# DRIVERS.net
KiCad netlist of a schematic drawn in Altium Designer
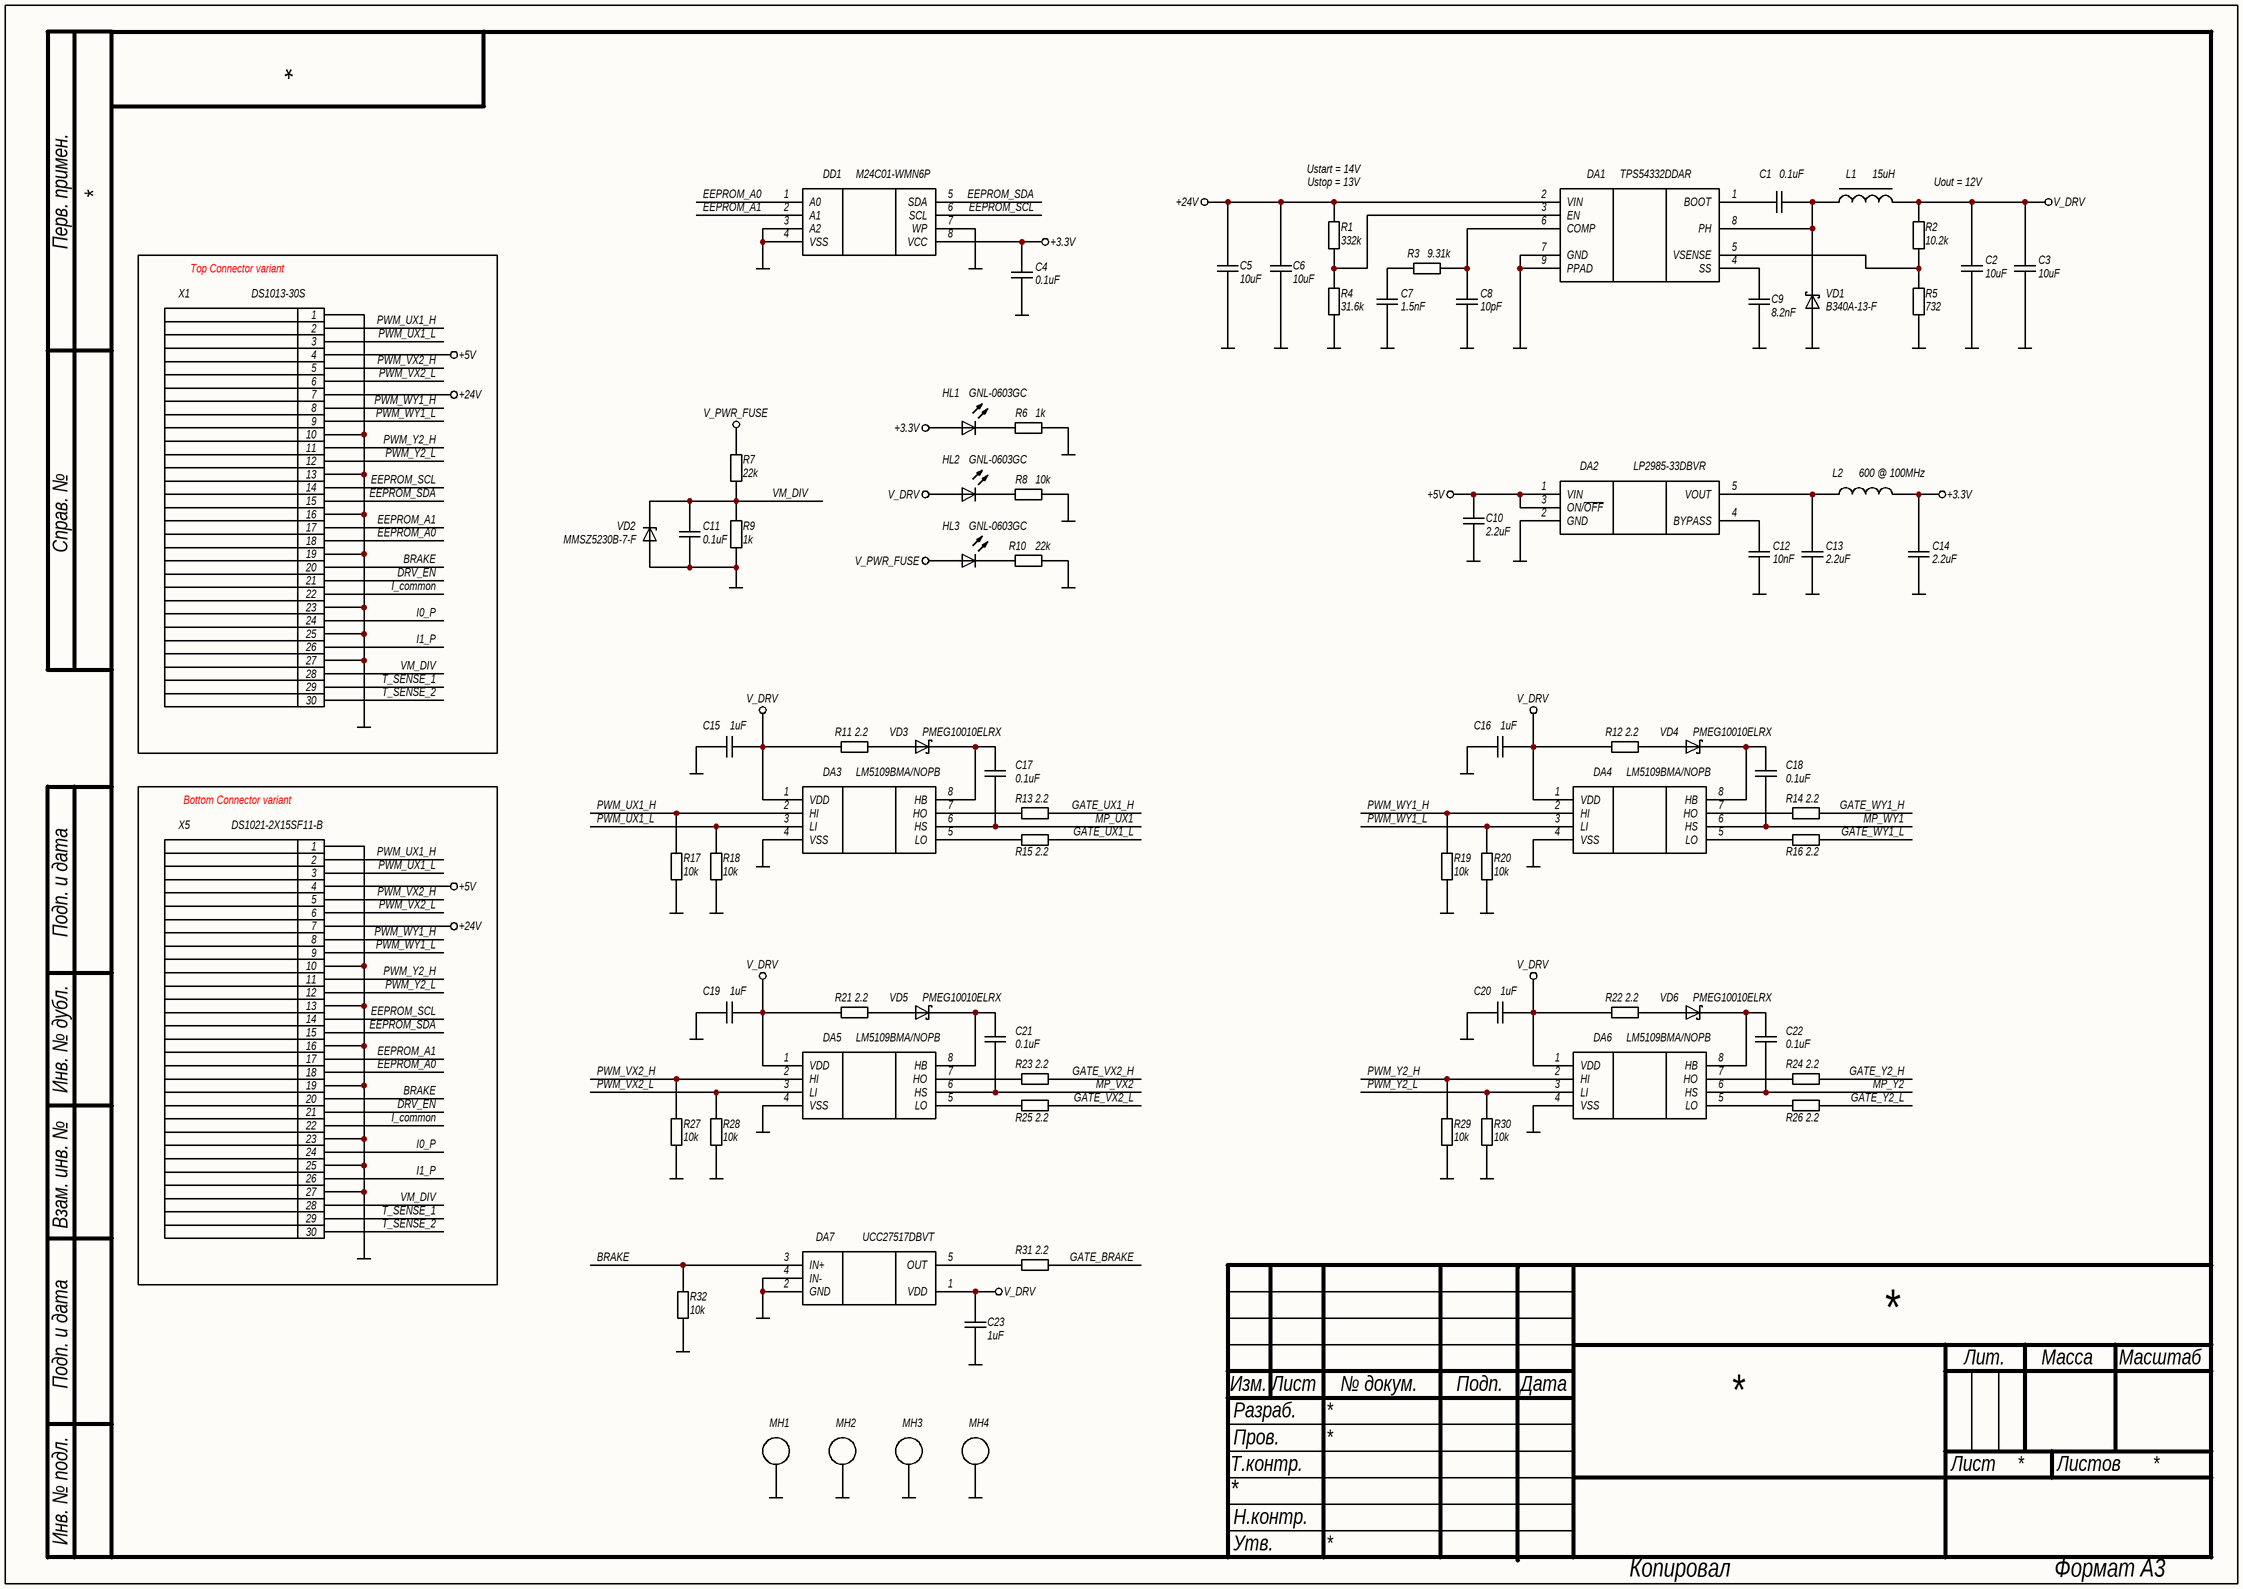
[diagram p0: DRIVERS.SchDoc]

(export (version "E")
  (design (tool "Eeschema 10.0.6"))
  (components
    (comp (ref "C1")
      (value "0.1uF")
      (footprint "C0603N")
      (description "Конденсатор")
      (libsource (lib "Components Library") (part "CAP_FIXED"))
    )
    (comp (ref "C2")
      (value "10uF")
      (footprint "C0805N")
      (description "Конденсатор")
      (libsource (lib "Components Library") (part "CAP_FIXED"))
    )
    (comp (ref "C3")
      (value "10uF")
      (footprint "C0805N")
      (description "Конденсатор")
      (libsource (lib "Components Library") (part "CAP_FIXED"))
    )
    (comp (ref "C4")
      (value "0.1uF")
      (footprint "C0603N")
      (description "Конденсатор")
      (libsource (lib "Components Library") (part "CAP_FIXED"))
    )
    (comp (ref "C5")
      (value "10uF")
      (footprint "C1206N")
      (description "Конденсатор")
      (libsource (lib "Components Library") (part "CAP_FIXED"))
    )
    (comp (ref "C6")
      (value "10uF")
      (footprint "C1206N")
      (description "Конденсатор")
      (libsource (lib "Components Library") (part "CAP_FIXED"))
    )
    (comp (ref "C7")
      (value "1.5nF")
      (footprint "C0603N")
      (description "Конденсатор")
      (libsource (lib "Components Library") (part "CAP_FIXED"))
    )
    (comp (ref "C8")
      (value "10pF")
      (footprint "C0603N")
      (description "Конденсатор")
      (libsource (lib "Components Library") (part "CAP_FIXED"))
    )
    (comp (ref "C9")
      (value "8.2nF")
      (footprint "C0603N")
      (description "Конденсатор")
      (libsource (lib "Components Library") (part "CAP_FIXED"))
    )
    (comp (ref "C10")
      (value "2.2uF")
      (footprint "C0603N")
      (description "Конденсатор")
      (libsource (lib "Components Library") (part "CAP_FIXED"))
    )
    (comp (ref "C11")
      (value "0.1uF")
      (footprint "C0603N")
      (description "Конденсатор")
      (libsource (lib "Components Library") (part "CAP_FIXED"))
    )
    (comp (ref "C12")
      (value "10nF")
      (footprint "C0603N")
      (description "Конденсатор")
      (libsource (lib "Components Library") (part "CAP_FIXED"))
    )
    (comp (ref "C13")
      (value "2.2uF")
      (footprint "C0603N")
      (description "Конденсатор")
      (libsource (lib "Components Library") (part "CAP_FIXED"))
    )
    (comp (ref "C14")
      (value "2.2uF")
      (footprint "C0603N")
      (description "Конденсатор")
      (libsource (lib "Components Library") (part "CAP_FIXED"))
    )
    (comp (ref "C15")
      (value "1uF")
      (footprint "C0805N")
      (description "Конденсатор")
      (libsource (lib "Components Library") (part "CAP_FIXED"))
    )
    (comp (ref "C16")
      (value "1uF")
      (footprint "C0805N")
      (description "Конденсатор")
      (libsource (lib "Components Library") (part "CAP_FIXED"))
    )
    (comp (ref "C17")
      (value "0.1uF")
      (footprint "C0603N")
      (description "Конденсатор")
      (libsource (lib "Components Library") (part "CAP_FIXED"))
    )
    (comp (ref "C18")
      (value "0.1uF")
      (footprint "C0603N")
      (description "Конденсатор")
      (libsource (lib "Components Library") (part "CAP_FIXED"))
    )
    (comp (ref "C19")
      (value "1uF")
      (footprint "C0805N")
      (description "Конденсатор")
      (libsource (lib "Components Library") (part "CAP_FIXED"))
    )
    (comp (ref "C20")
      (value "1uF")
      (footprint "C0805N")
      (description "Конденсатор")
      (libsource (lib "Components Library") (part "CAP_FIXED"))
    )
    (comp (ref "C21")
      (value "0.1uF")
      (footprint "C0603N")
      (description "Конденсатор")
      (libsource (lib "Components Library") (part "CAP_FIXED"))
    )
    (comp (ref "C22")
      (value "0.1uF")
      (footprint "C0603N")
      (description "Конденсатор")
      (libsource (lib "Components Library") (part "CAP_FIXED"))
    )
    (comp (ref "C23")
      (value "1uF")
      (footprint "C0805N")
      (description "Конденсатор")
      (libsource (lib "Components Library") (part "CAP_FIXED"))
    )
    (comp (ref "DA1")
      (value "TPS54332DDAR")
      (footprint "SOIC8-EP")
      (description "Микросхема понижающего преобразователя")
      (libsource (lib "Components Library") (part "TPS54332"))
    )
    (comp (ref "DA2")
      (value "LP2985-33DBVR")
      (footprint "DBV0005A (SOT23-5)")
      (description "Микросхема стабилизатор напряжения положительной полярности")
      (libsource (lib "Components Library") (part "LP2985"))
    )
    (comp (ref "DA3")
      (value "LM5109BMA/NOPB")
      (footprint "D0008A")
      (description "Микросхема драйвер затворов нижнего и верхнего ключа")
      (libsource (lib "Components Library") (part "LM5109"))
    )
    (comp (ref "DA4")
      (value "LM5109BMA/NOPB")
      (footprint "D0008A")
      (description "Микросхема драйвер затворов нижнего и верхнего ключа")
      (libsource (lib "Components Library") (part "LM5109"))
    )
    (comp (ref "DA5")
      (value "LM5109BMA/NOPB")
      (footprint "D0008A")
      (description "Микросхема драйвер затворов нижнего и верхнего ключа")
      (libsource (lib "Components Library") (part "LM5109"))
    )
    (comp (ref "DA6")
      (value "LM5109BMA/NOPB")
      (footprint "D0008A")
      (description "Микросхема драйвер затворов нижнего и верхнего ключа")
      (libsource (lib "Components Library") (part "LM5109"))
    )
    (comp (ref "DA7")
      (value "UCC27517DBVT")
      (footprint "DBV0005A (SOT23-5)")
      (description "Микросхема драйвер затвора нижнего ключа")
      (libsource (lib "Components Library") (part "UCC27517"))
    )
    (comp (ref "DD1")
      (value "M24C01-WMN6P")
      (footprint "SOIC8")
      (description "Микросхема EEPROM с I2C интерфейсом")
      (libsource (lib "Components Library") (part "EEPROM_I2C"))
    )
    (comp (ref "HL1")
      (value "GNL-0603GC")
      (footprint "LED0603")
      (description "Светодиод")
      (libsource (lib "Components Library") (part "LED"))
    )
    (comp (ref "HL2")
      (value "GNL-0603GC")
      (footprint "LED0603")
      (description "Светодиод")
      (libsource (lib "Components Library") (part "LED"))
    )
    (comp (ref "HL3")
      (value "GNL-0603GC")
      (footprint "LED0603")
      (description "Светодиод")
      (libsource (lib "Components Library") (part "LED"))
    )
    (comp (ref "L1")
      (value "15uH")
      (footprint "SRN8040")
      (description "Дроссель с магнитопроводом")
      (libsource (lib "Components Library") (part "IND_CORE"))
    )
    (comp (ref "L2")
      (value "600 @ 100MHz")
      (footprint "FB0603N")
      (description "Фильтр ЭМП индуктивный")
      (libsource (lib "Components Library") (part "IND_FILTER"))
    )
    (comp (ref "MH1")
      (value "MNT_HOLE_PL")
      (footprint "MH_3.2_5.4_PLATED_VIA")
      (description "Монтажное отверстие, металлизированное")
      (libsource (lib "Components Library") (part "MNT_HOLE_PL"))
    )
    (comp (ref "MH2")
      (value "MNT_HOLE_PL")
      (footprint "MH_3.2_5.4_PLATED_VIA")
      (description "Монтажное отверстие, металлизированное")
      (libsource (lib "Components Library") (part "MNT_HOLE_PL"))
    )
    (comp (ref "MH3")
      (value "MNT_HOLE_PL")
      (footprint "MH_3.2_5.4_PLATED_VIA")
      (description "Монтажное отверстие, металлизированное")
      (libsource (lib "Components Library") (part "MNT_HOLE_PL"))
    )
    (comp (ref "MH4")
      (value "MNT_HOLE_PL")
      (footprint "MH_3.2_5.4_PLATED_VIA")
      (description "Монтажное отверстие, металлизированное")
      (libsource (lib "Components Library") (part "MNT_HOLE_PL"))
    )
    (comp (ref "R1")
      (value "332k")
      (footprint "R0603N")
      (description "Резистор")
      (libsource (lib "Components Library") (part "RES_FIXED"))
    )
    (comp (ref "R2")
      (value "10.2k")
      (footprint "R0603N")
      (description "Резистор")
      (libsource (lib "Components Library") (part "RES_FIXED"))
    )
    (comp (ref "R3")
      (value "9.31k")
      (footprint "R0603N")
      (description "Резистор")
      (libsource (lib "") (part "RES_FIXED_1"))
    )
    (comp (ref "R4")
      (value "31.6k")
      (footprint "R0603N")
      (description "Резистор")
      (libsource (lib "Components Library") (part "RES_FIXED"))
    )
    (comp (ref "R5")
      (value "732")
      (footprint "R0603N")
      (description "Резистор")
      (libsource (lib "Components Library") (part "RES_FIXED"))
    )
    (comp (ref "R6")
      (value "1k")
      (footprint "R0603N")
      (description "Резистор")
      (libsource (lib "") (part "RES_FIXED_2"))
    )
    (comp (ref "R7")
      (value "22k")
      (footprint "R0603N")
      (description "Резистор")
      (libsource (lib "Components Library") (part "RES_FIXED"))
    )
    (comp (ref "R8")
      (value "10k")
      (footprint "R0603N")
      (description "Резистор")
      (libsource (lib "") (part "RES_FIXED_2"))
    )
    (comp (ref "R9")
      (value "1k")
      (footprint "R0603N")
      (description "Резистор")
      (libsource (lib "Components Library") (part "RES_FIXED"))
    )
    (comp (ref "R10")
      (value "22k")
      (footprint "R0603N")
      (description "Резистор")
      (libsource (lib "") (part "RES_FIXED_2"))
    )
    (comp (ref "R11")
      (value "2.2")
      (footprint "R0603N")
      (description "Резистор")
      (libsource (lib "") (part "RES_FIXED_1"))
    )
    (comp (ref "R12")
      (value "2.2")
      (footprint "R0603N")
      (description "Резистор")
      (libsource (lib "") (part "RES_FIXED_1"))
    )
    (comp (ref "R13")
      (value "2.2")
      (footprint "R0603N")
      (description "Резистор")
      (libsource (lib "") (part "RES_FIXED_1"))
    )
    (comp (ref "R14")
      (value "2.2")
      (footprint "R0603N")
      (description "Резистор")
      (libsource (lib "") (part "RES_FIXED_1"))
    )
    (comp (ref "R15")
      (value "2.2")
      (footprint "R0603N")
      (description "Резистор")
      (libsource (lib "") (part "RES_FIXED_1"))
    )
    (comp (ref "R16")
      (value "2.2")
      (footprint "R0603N")
      (description "Резистор")
      (libsource (lib "") (part "RES_FIXED_1"))
    )
    (comp (ref "R17")
      (value "10k")
      (footprint "R0603N")
      (description "Резистор")
      (libsource (lib "Components Library") (part "RES_FIXED"))
    )
    (comp (ref "R18")
      (value "10k")
      (footprint "R0603N")
      (description "Резистор")
      (libsource (lib "Components Library") (part "RES_FIXED"))
    )
    (comp (ref "R19")
      (value "10k")
      (footprint "R0603N")
      (description "Резистор")
      (libsource (lib "Components Library") (part "RES_FIXED"))
    )
    (comp (ref "R20")
      (value "10k")
      (footprint "R0603N")
      (description "Резистор")
      (libsource (lib "Components Library") (part "RES_FIXED"))
    )
    (comp (ref "R21")
      (value "2.2")
      (footprint "R0603N")
      (description "Резистор")
      (libsource (lib "") (part "RES_FIXED_1"))
    )
    (comp (ref "R22")
      (value "2.2")
      (footprint "R0603N")
      (description "Резистор")
      (libsource (lib "") (part "RES_FIXED_1"))
    )
    (comp (ref "R23")
      (value "2.2")
      (footprint "R0603N")
      (description "Резистор")
      (libsource (lib "") (part "RES_FIXED_1"))
    )
    (comp (ref "R24")
      (value "2.2")
      (footprint "R0603N")
      (description "Резистор")
      (libsource (lib "") (part "RES_FIXED_1"))
    )
    (comp (ref "R25")
      (value "2.2")
      (footprint "R0603N")
      (description "Резистор")
      (libsource (lib "") (part "RES_FIXED_1"))
    )
    (comp (ref "R26")
      (value "2.2")
      (footprint "R0603N")
      (description "Резистор")
      (libsource (lib "") (part "RES_FIXED_1"))
    )
    (comp (ref "R27")
      (value "10k")
      (footprint "R0603N")
      (description "Резистор")
      (libsource (lib "Components Library") (part "RES_FIXED"))
    )
    (comp (ref "R28")
      (value "10k")
      (footprint "R0603N")
      (description "Резистор")
      (libsource (lib "Components Library") (part "RES_FIXED"))
    )
    (comp (ref "R29")
      (value "10k")
      (footprint "R0603N")
      (description "Резистор")
      (libsource (lib "Components Library") (part "RES_FIXED"))
    )
    (comp (ref "R30")
      (value "10k")
      (footprint "R0603N")
      (description "Резистор")
      (libsource (lib "Components Library") (part "RES_FIXED"))
    )
    (comp (ref "R31")
      (value "2.2")
      (footprint "R0603N")
      (description "Резистор")
      (libsource (lib "") (part "RES_FIXED_1"))
    )
    (comp (ref "R32")
      (value "10k")
      (footprint "R0603N")
      (description "Резистор")
      (libsource (lib "Components Library") (part "RES_FIXED"))
    )
    (comp (ref "VD1")
      (value "B340A-13-F")
      (footprint "SMA")
      (description "Диод Шоттки")
      (libsource (lib "Components Library") (part "SCHOTTKY"))
    )
    (comp (ref "VD2")
      (value "MMSZ5230B-7-F")
      (footprint "SOD123")
      (description "Стабилитрон")
      (libsource (lib "Components Library") (part "ZENER"))
    )
    (comp (ref "VD3")
      (value "PMEG10010ELRX")
      (footprint "SOD123W")
      (description "Диод Шоттки")
      (libsource (lib "Components Library") (part "SCHOTTKY"))
    )
    (comp (ref "VD4")
      (value "PMEG10010ELRX")
      (footprint "SOD123W")
      (description "Диод Шоттки")
      (libsource (lib "Components Library") (part "SCHOTTKY"))
    )
    (comp (ref "VD5")
      (value "PMEG10010ELRX")
      (footprint "SOD123W")
      (description "Диод Шоттки")
      (libsource (lib "Components Library") (part "SCHOTTKY"))
    )
    (comp (ref "VD6")
      (value "PMEG10010ELRX")
      (footprint "SOD123W")
      (description "Диод Шоттки")
      (libsource (lib "Components Library") (part "SCHOTTKY"))
    )
    (comp (ref "X1")
      (value "DS1013-30S")
      (footprint "2.54_2X15_HEADER_BOX")
      (description "Разъем, 30 контактов")
      (libsource (lib "Components Library") (part "Connector 30"))
    )
    (comp (ref "X5")
      (value "DS1021-2X15SF11-B")
      (footprint "2.54_2X15_HEADER")
      (description "Разъем, 30 контактов")
      (libsource (lib "Components Library") (part "Connector 30"))
    )
  )
  (nets
    (net (code "1") (name "+3.3V") (class "Default")
      (node (ref "C14") (pin "2") (pinfunction "2_2") (pintype "passive"))
      (node (ref "C4") (pin "2") (pinfunction "2_2") (pintype "passive"))
      (node (ref "DD1") (pin "8") (pinfunction "VCC_8") (pintype "power_in"))
      (node (ref "HL1") (pin "2") (pinfunction "A_2") (pintype "passive"))
      (node (ref "L2") (pin "2") (pinfunction "2_2") (pintype "passive"))
    )
    (net (code "2") (name "+5V") (class "Default")
      (node (ref "C10") (pin "2") (pinfunction "2_2") (pintype "passive"))
      (node (ref "DA2") (pin "1") (pinfunction "VIN_1") (pintype "power_in"))
      (node (ref "DA2") (pin "3") (pinfunction "ON/~{OFF}_3") (pintype "power_in"))
      (node (ref "X1") (pin "4") (pinfunction "4_4") (pintype "power_in"))
      (node (ref "X5") (pin "4") (pinfunction "4_4") (pintype "power_in"))
    )
    (net (code "3") (name "+24V") (class "Default")
      (node (ref "C5") (pin "2") (pinfunction "2_2") (pintype "passive"))
      (node (ref "C6") (pin "2") (pinfunction "2_2") (pintype "passive"))
      (node (ref "DA1") (pin "2") (pinfunction "VIN_2") (pintype "power_in"))
      (node (ref "R1") (pin "1") (pinfunction "1_1") (pintype "passive"))
      (node (ref "X1") (pin "7") (pinfunction "7_7") (pintype "power_in"))
      (node (ref "X5") (pin "7") (pinfunction "7_7") (pintype "power_in"))
    )
    (net (code "4") (name "/BRAKE") (class "Default")
      (node (ref "DA7") (pin "3") (pinfunction "IN+_3") (pintype "power_in"))
      (node (ref "R32") (pin "1") (pinfunction "1_1") (pintype "passive"))
      (node (ref "X1") (pin "20") (pinfunction "20_20") (pintype "power_in"))
      (node (ref "X5") (pin "20") (pinfunction "20_20") (pintype "power_in"))
    )
    (net (code "5") (name "/DRV_EN") (class "Default")
      (node (ref "X1") (pin "21") (pinfunction "21_21") (pintype "power_in"))
      (node (ref "X5") (pin "21") (pinfunction "21_21") (pintype "power_in"))
    )
    (net (code "6") (name "/EEPROM_A0") (class "Default")
      (node (ref "DD1") (pin "1") (pinfunction "A0_1") (pintype "power_in"))
      (node (ref "X1") (pin "18") (pinfunction "18_18") (pintype "power_in"))
      (node (ref "X5") (pin "18") (pinfunction "18_18") (pintype "power_in"))
    )
    (net (code "7") (name "/EEPROM_A1") (class "Default")
      (node (ref "DD1") (pin "2") (pinfunction "A1_2") (pintype "power_in"))
      (node (ref "X1") (pin "17") (pinfunction "17_17") (pintype "power_in"))
      (node (ref "X5") (pin "17") (pinfunction "17_17") (pintype "power_in"))
    )
    (net (code "8") (name "/EEPROM_SCL") (class "Default")
      (node (ref "DD1") (pin "6") (pinfunction "SCL_6") (pintype "power_in"))
      (node (ref "X1") (pin "14") (pinfunction "14_14") (pintype "power_in"))
      (node (ref "X5") (pin "14") (pinfunction "14_14") (pintype "power_in"))
    )
    (net (code "9") (name "/EEPROM_SDA") (class "Default")
      (node (ref "DD1") (pin "5") (pinfunction "SDA_5") (pintype "power_in"))
      (node (ref "X1") (pin "15") (pinfunction "15_15") (pintype "power_in"))
      (node (ref "X5") (pin "15") (pinfunction "15_15") (pintype "power_in"))
    )
    (net (code "10") (name "/GATE_BRAKE") (class "Default")
      (node (ref "R31") (pin "1") (pinfunction "1_1") (pintype "passive"))
    )
    (net (code "11") (name "/GATE_UX1_H") (class "Default")
      (node (ref "R13") (pin "1") (pinfunction "1_1") (pintype "passive"))
    )
    (net (code "12") (name "/GATE_UX1_L") (class "Default")
      (node (ref "R15") (pin "1") (pinfunction "1_1") (pintype "passive"))
    )
    (net (code "13") (name "/GATE_VX2_H") (class "Default")
      (node (ref "R23") (pin "1") (pinfunction "1_1") (pintype "passive"))
    )
    (net (code "14") (name "/GATE_VX2_L") (class "Default")
      (node (ref "R25") (pin "1") (pinfunction "1_1") (pintype "passive"))
    )
    (net (code "15") (name "/GATE_WY1_H") (class "Default")
      (node (ref "R14") (pin "1") (pinfunction "1_1") (pintype "passive"))
    )
    (net (code "16") (name "/GATE_WY1_L") (class "Default")
      (node (ref "R16") (pin "1") (pinfunction "1_1") (pintype "passive"))
    )
    (net (code "17") (name "/GATE_Y2_H") (class "Default")
      (node (ref "R24") (pin "1") (pinfunction "1_1") (pintype "passive"))
    )
    (net (code "18") (name "/GATE_Y2_L") (class "Default")
      (node (ref "R26") (pin "1") (pinfunction "1_1") (pintype "passive"))
    )
    (net (code "19") (name "/I0_P") (class "Default")
      (node (ref "X1") (pin "24") (pinfunction "24_24") (pintype "power_in"))
      (node (ref "X5") (pin "24") (pinfunction "24_24") (pintype "power_in"))
    )
    (net (code "20") (name "/I1_P") (class "Default")
      (node (ref "X1") (pin "26") (pinfunction "26_26") (pintype "power_in"))
      (node (ref "X5") (pin "26") (pinfunction "26_26") (pintype "power_in"))
    )
    (net (code "21") (name "/I_common") (class "Default")
      (node (ref "X1") (pin "22") (pinfunction "22_22") (pintype "power_in"))
      (node (ref "X5") (pin "22") (pinfunction "22_22") (pintype "power_in"))
    )
    (net (code "22") (name "/MP_UX1") (class "Default")
      (node (ref "C17") (pin "2") (pinfunction "2_2") (pintype "passive"))
      (node (ref "DA3") (pin "6") (pinfunction "HS_6") (pintype "power_in"))
    )
    (net (code "23") (name "/MP_VX2") (class "Default")
      (node (ref "C21") (pin "2") (pinfunction "2_2") (pintype "passive"))
      (node (ref "DA5") (pin "6") (pinfunction "HS_6") (pintype "power_in"))
    )
    (net (code "24") (name "/MP_WY1") (class "Default")
      (node (ref "C18") (pin "2") (pinfunction "2_2") (pintype "passive"))
      (node (ref "DA4") (pin "6") (pinfunction "HS_6") (pintype "power_in"))
    )
    (net (code "25") (name "/MP_Y2") (class "Default")
      (node (ref "C22") (pin "2") (pinfunction "2_2") (pintype "passive"))
      (node (ref "DA6") (pin "6") (pinfunction "HS_6") (pintype "power_in"))
    )
    (net (code "26") (name "/PWM_UX1_H") (class "Default")
      (node (ref "DA3") (pin "2") (pinfunction "HI_2") (pintype "power_in"))
      (node (ref "R17") (pin "1") (pinfunction "1_1") (pintype "passive"))
      (node (ref "X1") (pin "2") (pinfunction "2_2") (pintype "power_in"))
      (node (ref "X5") (pin "2") (pinfunction "2_2") (pintype "power_in"))
    )
    (net (code "27") (name "/PWM_UX1_L") (class "Default")
      (node (ref "DA3") (pin "3") (pinfunction "LI_3") (pintype "power_in"))
      (node (ref "R18") (pin "1") (pinfunction "1_1") (pintype "passive"))
      (node (ref "X1") (pin "3") (pinfunction "3_3") (pintype "power_in"))
      (node (ref "X5") (pin "3") (pinfunction "3_3") (pintype "power_in"))
    )
    (net (code "28") (name "/PWM_VX2_H") (class "Default")
      (node (ref "DA5") (pin "2") (pinfunction "HI_2") (pintype "power_in"))
      (node (ref "R27") (pin "1") (pinfunction "1_1") (pintype "passive"))
      (node (ref "X1") (pin "5") (pinfunction "5_5") (pintype "power_in"))
      (node (ref "X5") (pin "5") (pinfunction "5_5") (pintype "power_in"))
    )
    (net (code "29") (name "/PWM_VX2_L") (class "Default")
      (node (ref "DA5") (pin "3") (pinfunction "LI_3") (pintype "power_in"))
      (node (ref "R28") (pin "1") (pinfunction "1_1") (pintype "passive"))
      (node (ref "X1") (pin "6") (pinfunction "6_6") (pintype "power_in"))
      (node (ref "X5") (pin "6") (pinfunction "6_6") (pintype "power_in"))
    )
    (net (code "30") (name "/PWM_WY1_H") (class "Default")
      (node (ref "DA4") (pin "2") (pinfunction "HI_2") (pintype "power_in"))
      (node (ref "R19") (pin "1") (pinfunction "1_1") (pintype "passive"))
      (node (ref "X1") (pin "8") (pinfunction "8_8") (pintype "power_in"))
      (node (ref "X5") (pin "8") (pinfunction "8_8") (pintype "power_in"))
    )
    (net (code "31") (name "/PWM_WY1_L") (class "Default")
      (node (ref "DA4") (pin "3") (pinfunction "LI_3") (pintype "power_in"))
      (node (ref "R20") (pin "1") (pinfunction "1_1") (pintype "passive"))
      (node (ref "X1") (pin "9") (pinfunction "9_9") (pintype "power_in"))
      (node (ref "X5") (pin "9") (pinfunction "9_9") (pintype "power_in"))
    )
    (net (code "32") (name "/PWM_Y2_H") (class "Default")
      (node (ref "DA6") (pin "2") (pinfunction "HI_2") (pintype "power_in"))
      (node (ref "R29") (pin "1") (pinfunction "1_1") (pintype "passive"))
      (node (ref "X1") (pin "11") (pinfunction "11_11") (pintype "power_in"))
      (node (ref "X5") (pin "11") (pinfunction "11_11") (pintype "power_in"))
    )
    (net (code "33") (name "/PWM_Y2_L") (class "Default")
      (node (ref "DA6") (pin "3") (pinfunction "LI_3") (pintype "power_in"))
      (node (ref "R30") (pin "1") (pinfunction "1_1") (pintype "passive"))
      (node (ref "X1") (pin "12") (pinfunction "12_12") (pintype "power_in"))
      (node (ref "X5") (pin "12") (pinfunction "12_12") (pintype "power_in"))
    )
    (net (code "34") (name "/T_SENSE_1") (class "Default")
      (node (ref "X1") (pin "29") (pinfunction "29_29") (pintype "power_in"))
      (node (ref "X5") (pin "29") (pinfunction "29_29") (pintype "power_in"))
    )
    (net (code "35") (name "/T_SENSE_2") (class "Default")
      (node (ref "X1") (pin "30") (pinfunction "30_30") (pintype "power_in"))
      (node (ref "X5") (pin "30") (pinfunction "30_30") (pintype "power_in"))
    )
    (net (code "36") (name "/VM_DIV") (class "Default")
      (node (ref "C11") (pin "2") (pinfunction "2_2") (pintype "passive"))
      (node (ref "R7") (pin "2") (pinfunction "2_2") (pintype "passive"))
      (node (ref "R9") (pin "1") (pinfunction "1_1") (pintype "passive"))
      (node (ref "VD2") (pin "1") (pinfunction "K_1") (pintype "passive"))
      (node (ref "X1") (pin "28") (pinfunction "28_28") (pintype "power_in"))
      (node (ref "X5") (pin "28") (pinfunction "28_28") (pintype "power_in"))
    )
    (net (code "37") (name "GND") (class "Default")
      (node (ref "C10") (pin "1") (pinfunction "1_1") (pintype "passive"))
      (node (ref "C11") (pin "1") (pinfunction "1_1") (pintype "passive"))
      (node (ref "C12") (pin "1") (pinfunction "1_1") (pintype "passive"))
      (node (ref "C13") (pin "1") (pinfunction "1_1") (pintype "passive"))
      (node (ref "C14") (pin "1") (pinfunction "1_1") (pintype "passive"))
      (node (ref "C15") (pin "2") (pinfunction "2_2") (pintype "passive"))
      (node (ref "C16") (pin "2") (pinfunction "2_2") (pintype "passive"))
      (node (ref "C19") (pin "2") (pinfunction "2_2") (pintype "passive"))
      (node (ref "C2") (pin "2") (pinfunction "2_2") (pintype "passive"))
      (node (ref "C20") (pin "2") (pinfunction "2_2") (pintype "passive"))
      (node (ref "C23") (pin "2") (pinfunction "2_2") (pintype "passive"))
      (node (ref "C3") (pin "1") (pinfunction "1_1") (pintype "passive"))
      (node (ref "C4") (pin "1") (pinfunction "1_1") (pintype "passive"))
      (node (ref "C5") (pin "1") (pinfunction "1_1") (pintype "passive"))
      (node (ref "C6") (pin "1") (pinfunction "1_1") (pintype "passive"))
      (node (ref "C7") (pin "1") (pinfunction "1_1") (pintype "passive"))
      (node (ref "C8") (pin "1") (pinfunction "1_1") (pintype "passive"))
      (node (ref "C9") (pin "1") (pinfunction "1_1") (pintype "passive"))
      (node (ref "DA1") (pin "7") (pinfunction "GND_7") (pintype "power_in"))
      (node (ref "DA1") (pin "9") (pinfunction "PPAD_9") (pintype "power_in"))
      (node (ref "DA2") (pin "2") (pinfunction "GND_2") (pintype "power_in"))
      (node (ref "DA3") (pin "4") (pinfunction "VSS_4") (pintype "power_in"))
      (node (ref "DA4") (pin "4") (pinfunction "VSS_4") (pintype "power_in"))
      (node (ref "DA5") (pin "4") (pinfunction "VSS_4") (pintype "power_in"))
      (node (ref "DA6") (pin "4") (pinfunction "VSS_4") (pintype "power_in"))
      (node (ref "DA7") (pin "2") (pinfunction "GND_2") (pintype "power_in"))
      (node (ref "DA7") (pin "4") (pinfunction "IN-_4") (pintype "power_in"))
      (node (ref "DD1") (pin "3") (pinfunction "A2_3") (pintype "power_in"))
      (node (ref "DD1") (pin "4") (pinfunction "VSS_4") (pintype "power_in"))
      (node (ref "DD1") (pin "7") (pinfunction "WP_7") (pintype "power_in"))
      (node (ref "MH1") (pin "1") (pinfunction "1_1") (pintype "passive"))
      (node (ref "MH2") (pin "1") (pinfunction "1_1") (pintype "passive"))
      (node (ref "MH3") (pin "1") (pinfunction "1_1") (pintype "passive"))
      (node (ref "MH4") (pin "1") (pinfunction "1_1") (pintype "passive"))
      (node (ref "R10") (pin "2") (pinfunction "2_2") (pintype "passive"))
      (node (ref "R17") (pin "2") (pinfunction "2_2") (pintype "passive"))
      (node (ref "R18") (pin "2") (pinfunction "2_2") (pintype "passive"))
      (node (ref "R19") (pin "2") (pinfunction "2_2") (pintype "passive"))
      (node (ref "R20") (pin "2") (pinfunction "2_2") (pintype "passive"))
      (node (ref "R27") (pin "2") (pinfunction "2_2") (pintype "passive"))
      (node (ref "R28") (pin "2") (pinfunction "2_2") (pintype "passive"))
      (node (ref "R29") (pin "2") (pinfunction "2_2") (pintype "passive"))
      (node (ref "R30") (pin "2") (pinfunction "2_2") (pintype "passive"))
      (node (ref "R32") (pin "2") (pinfunction "2_2") (pintype "passive"))
      (node (ref "R4") (pin "2") (pinfunction "2_2") (pintype "passive"))
      (node (ref "R5") (pin "2") (pinfunction "2_2") (pintype "passive"))
      (node (ref "R6") (pin "2") (pinfunction "2_2") (pintype "passive"))
      (node (ref "R8") (pin "2") (pinfunction "2_2") (pintype "passive"))
      (node (ref "R9") (pin "2") (pinfunction "2_2") (pintype "passive"))
      (node (ref "VD1") (pin "2") (pinfunction "A_2") (pintype "passive"))
      (node (ref "VD2") (pin "2") (pinfunction "A_2") (pintype "passive"))
      (node (ref "X1") (pin "1") (pinfunction "1_1") (pintype "power_in"))
      (node (ref "X1") (pin "10") (pinfunction "10_10") (pintype "power_in"))
      (node (ref "X1") (pin "13") (pinfunction "13_13") (pintype "power_in"))
      (node (ref "X1") (pin "16") (pinfunction "16_16") (pintype "power_in"))
      (node (ref "X1") (pin "19") (pinfunction "19_19") (pintype "power_in"))
      (node (ref "X1") (pin "23") (pinfunction "23_23") (pintype "power_in"))
      (node (ref "X1") (pin "25") (pinfunction "25_25") (pintype "power_in"))
      (node (ref "X1") (pin "27") (pinfunction "27_27") (pintype "power_in"))
      (node (ref "X5") (pin "1") (pinfunction "1_1") (pintype "power_in"))
      (node (ref "X5") (pin "10") (pinfunction "10_10") (pintype "power_in"))
      (node (ref "X5") (pin "13") (pinfunction "13_13") (pintype "power_in"))
      (node (ref "X5") (pin "16") (pinfunction "16_16") (pintype "power_in"))
      (node (ref "X5") (pin "19") (pinfunction "19_19") (pintype "power_in"))
      (node (ref "X5") (pin "23") (pinfunction "23_23") (pintype "power_in"))
      (node (ref "X5") (pin "25") (pinfunction "25_25") (pintype "power_in"))
      (node (ref "X5") (pin "27") (pinfunction "27_27") (pintype "power_in"))
    )
    (net (code "38") (name "Net-(C7-Pad2)") (class "Default")
      (node (ref "C7") (pin "2") (pinfunction "2_2") (pintype "passive"))
      (node (ref "R3") (pin "2") (pinfunction "2_2") (pintype "passive"))
    )
    (net (code "39") (name "Net-(DA1-BOOT)") (class "Default")
      (node (ref "C1") (pin "1") (pinfunction "1_1") (pintype "passive"))
      (node (ref "DA1") (pin "1") (pinfunction "BOOT_1") (pintype "power_in"))
    )
    (net (code "40") (name "Net-(DA1-COMP)") (class "Default")
      (node (ref "C8") (pin "2") (pinfunction "2_2") (pintype "passive"))
      (node (ref "DA1") (pin "6") (pinfunction "COMP_6") (pintype "power_in"))
      (node (ref "R3") (pin "1") (pinfunction "1_1") (pintype "passive"))
    )
    (net (code "41") (name "Net-(DA1-EN)") (class "Default")
      (node (ref "DA1") (pin "3") (pinfunction "EN_3") (pintype "power_in"))
      (node (ref "R1") (pin "2") (pinfunction "2_2") (pintype "passive"))
      (node (ref "R4") (pin "1") (pinfunction "1_1") (pintype "passive"))
    )
    (net (code "42") (name "Net-(DA1-PH)") (class "Default")
      (node (ref "C1") (pin "2") (pinfunction "2_2") (pintype "passive"))
      (node (ref "DA1") (pin "8") (pinfunction "PH_8") (pintype "power_in"))
      (node (ref "L1") (pin "1") (pinfunction "1_1") (pintype "passive"))
      (node (ref "VD1") (pin "1") (pinfunction "K_1") (pintype "passive"))
    )
    (net (code "43") (name "Net-(DA1-SS)") (class "Default")
      (node (ref "C9") (pin "2") (pinfunction "2_2") (pintype "passive"))
      (node (ref "DA1") (pin "4") (pinfunction "SS_4") (pintype "power_in"))
    )
    (net (code "44") (name "Net-(DA1-VSENSE)") (class "Default")
      (node (ref "DA1") (pin "5") (pinfunction "VSENSE_5") (pintype "power_in"))
      (node (ref "R2") (pin "2") (pinfunction "2_2") (pintype "passive"))
      (node (ref "R5") (pin "1") (pinfunction "1_1") (pintype "passive"))
    )
    (net (code "45") (name "Net-(DA2-BYPASS)") (class "Default")
      (node (ref "C12") (pin "2") (pinfunction "2_2") (pintype "passive"))
      (node (ref "DA2") (pin "4") (pinfunction "BYPASS_4") (pintype "power_in"))
    )
    (net (code "46") (name "Net-(DA2-VOUT)") (class "Default")
      (node (ref "C13") (pin "2") (pinfunction "2_2") (pintype "passive"))
      (node (ref "DA2") (pin "5") (pinfunction "VOUT_5") (pintype "power_in"))
      (node (ref "L2") (pin "1") (pinfunction "1_1") (pintype "passive"))
    )
    (net (code "47") (name "Net-(DA3-HB)") (class "Default")
      (node (ref "C17") (pin "1") (pinfunction "1_1") (pintype "passive"))
      (node (ref "DA3") (pin "8") (pinfunction "HB_8") (pintype "power_in"))
      (node (ref "VD3") (pin "1") (pinfunction "K_1") (pintype "passive"))
    )
    (net (code "48") (name "Net-(DA3-HO)") (class "Default")
      (node (ref "DA3") (pin "7") (pinfunction "HO_7") (pintype "power_in"))
      (node (ref "R13") (pin "2") (pinfunction "2_2") (pintype "passive"))
    )
    (net (code "49") (name "Net-(DA3-LO)") (class "Default")
      (node (ref "DA3") (pin "5") (pinfunction "LO_5") (pintype "power_in"))
      (node (ref "R15") (pin "2") (pinfunction "2_2") (pintype "passive"))
    )
    (net (code "50") (name "Net-(DA4-HB)") (class "Default")
      (node (ref "C18") (pin "1") (pinfunction "1_1") (pintype "passive"))
      (node (ref "DA4") (pin "8") (pinfunction "HB_8") (pintype "power_in"))
      (node (ref "VD4") (pin "1") (pinfunction "K_1") (pintype "passive"))
    )
    (net (code "51") (name "Net-(DA4-HO)") (class "Default")
      (node (ref "DA4") (pin "7") (pinfunction "HO_7") (pintype "power_in"))
      (node (ref "R14") (pin "2") (pinfunction "2_2") (pintype "passive"))
    )
    (net (code "52") (name "Net-(DA4-LO)") (class "Default")
      (node (ref "DA4") (pin "5") (pinfunction "LO_5") (pintype "power_in"))
      (node (ref "R16") (pin "2") (pinfunction "2_2") (pintype "passive"))
    )
    (net (code "53") (name "Net-(DA5-HB)") (class "Default")
      (node (ref "C21") (pin "1") (pinfunction "1_1") (pintype "passive"))
      (node (ref "DA5") (pin "8") (pinfunction "HB_8") (pintype "power_in"))
      (node (ref "VD5") (pin "1") (pinfunction "K_1") (pintype "passive"))
    )
    (net (code "54") (name "Net-(DA5-HO)") (class "Default")
      (node (ref "DA5") (pin "7") (pinfunction "HO_7") (pintype "power_in"))
      (node (ref "R23") (pin "2") (pinfunction "2_2") (pintype "passive"))
    )
    (net (code "55") (name "Net-(DA5-LO)") (class "Default")
      (node (ref "DA5") (pin "5") (pinfunction "LO_5") (pintype "power_in"))
      (node (ref "R25") (pin "2") (pinfunction "2_2") (pintype "passive"))
    )
    (net (code "56") (name "Net-(DA6-HB)") (class "Default")
      (node (ref "C22") (pin "1") (pinfunction "1_1") (pintype "passive"))
      (node (ref "DA6") (pin "8") (pinfunction "HB_8") (pintype "power_in"))
      (node (ref "VD6") (pin "1") (pinfunction "K_1") (pintype "passive"))
    )
    (net (code "57") (name "Net-(DA6-HO)") (class "Default")
      (node (ref "DA6") (pin "7") (pinfunction "HO_7") (pintype "power_in"))
      (node (ref "R24") (pin "2") (pinfunction "2_2") (pintype "passive"))
    )
    (net (code "58") (name "Net-(DA6-LO)") (class "Default")
      (node (ref "DA6") (pin "5") (pinfunction "LO_5") (pintype "power_in"))
      (node (ref "R26") (pin "2") (pinfunction "2_2") (pintype "passive"))
    )
    (net (code "59") (name "Net-(DA7-OUT)") (class "Default")
      (node (ref "DA7") (pin "5") (pinfunction "OUT_5") (pintype "power_in"))
      (node (ref "R31") (pin "2") (pinfunction "2_2") (pintype "passive"))
    )
    (net (code "60") (name "Net-(HL1-K)") (class "Default")
      (node (ref "HL1") (pin "1") (pinfunction "K_1") (pintype "passive"))
      (node (ref "R6") (pin "1") (pinfunction "1_1") (pintype "passive"))
    )
    (net (code "61") (name "Net-(HL2-K)") (class "Default")
      (node (ref "HL2") (pin "1") (pinfunction "K_1") (pintype "passive"))
      (node (ref "R8") (pin "1") (pinfunction "1_1") (pintype "passive"))
    )
    (net (code "62") (name "Net-(HL3-K)") (class "Default")
      (node (ref "HL3") (pin "1") (pinfunction "K_1") (pintype "passive"))
      (node (ref "R10") (pin "1") (pinfunction "1_1") (pintype "passive"))
    )
    (net (code "63") (name "Net-(VD3-A)") (class "Default")
      (node (ref "R11") (pin "1") (pinfunction "1_1") (pintype "passive"))
      (node (ref "VD3") (pin "2") (pinfunction "A_2") (pintype "passive"))
    )
    (net (code "64") (name "Net-(VD4-A)") (class "Default")
      (node (ref "R12") (pin "1") (pinfunction "1_1") (pintype "passive"))
      (node (ref "VD4") (pin "2") (pinfunction "A_2") (pintype "passive"))
    )
    (net (code "65") (name "Net-(VD5-A)") (class "Default")
      (node (ref "R21") (pin "1") (pinfunction "1_1") (pintype "passive"))
      (node (ref "VD5") (pin "2") (pinfunction "A_2") (pintype "passive"))
    )
    (net (code "66") (name "Net-(VD6-A)") (class "Default")
      (node (ref "R22") (pin "1") (pinfunction "1_1") (pintype "passive"))
      (node (ref "VD6") (pin "2") (pinfunction "A_2") (pintype "passive"))
    )
    (net (code "67") (name "V_DRV") (class "Default")
      (node (ref "C15") (pin "1") (pinfunction "1_1") (pintype "passive"))
      (node (ref "C16") (pin "1") (pinfunction "1_1") (pintype "passive"))
      (node (ref "C19") (pin "1") (pinfunction "1_1") (pintype "passive"))
      (node (ref "C2") (pin "1") (pinfunction "1_1") (pintype "passive"))
      (node (ref "C20") (pin "1") (pinfunction "1_1") (pintype "passive"))
      (node (ref "C23") (pin "1") (pinfunction "1_1") (pintype "passive"))
      (node (ref "C3") (pin "2") (pinfunction "2_2") (pintype "passive"))
      (node (ref "DA3") (pin "1") (pinfunction "VDD_1") (pintype "power_in"))
      (node (ref "DA4") (pin "1") (pinfunction "VDD_1") (pintype "power_in"))
      (node (ref "DA5") (pin "1") (pinfunction "VDD_1") (pintype "power_in"))
      (node (ref "DA6") (pin "1") (pinfunction "VDD_1") (pintype "power_in"))
      (node (ref "DA7") (pin "1") (pinfunction "VDD_1") (pintype "power_in"))
      (node (ref "HL2") (pin "2") (pinfunction "A_2") (pintype "passive"))
      (node (ref "L1") (pin "2") (pinfunction "2_2") (pintype "passive"))
      (node (ref "R11") (pin "2") (pinfunction "2_2") (pintype "passive"))
      (node (ref "R12") (pin "2") (pinfunction "2_2") (pintype "passive"))
      (node (ref "R2") (pin "1") (pinfunction "1_1") (pintype "passive"))
      (node (ref "R21") (pin "2") (pinfunction "2_2") (pintype "passive"))
      (node (ref "R22") (pin "2") (pinfunction "2_2") (pintype "passive"))
    )
    (net (code "68") (name "V_PWR_FUSE") (class "Default")
      (node (ref "HL3") (pin "2") (pinfunction "A_2") (pintype "passive"))
      (node (ref "R7") (pin "1") (pinfunction "1_1") (pintype "passive"))
    )
  )
)
